# USB.net
KiCad netlist of a schematic drawn in Altium Designer
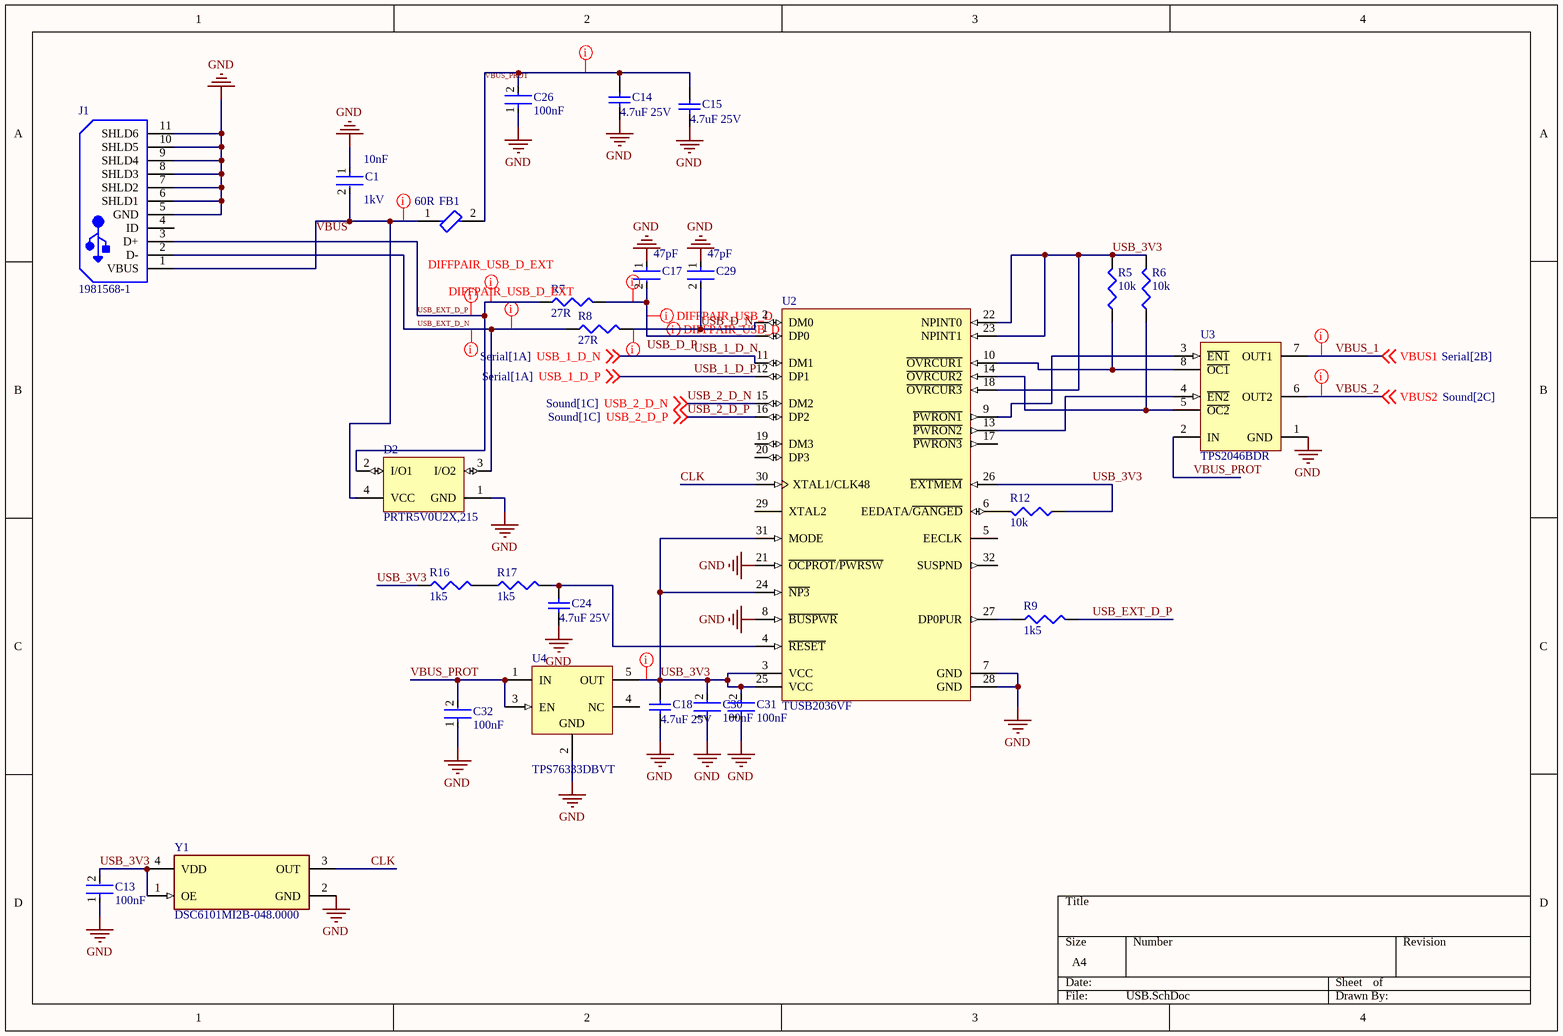
[diagram p0: USB.SchDoc]

(export (version "E")
  (design (tool "Eeschema 10.0.6"))
  (components
    (comp (ref "C1")
      (value "C4532X7R3A103K200KA")
      (footprint "FP-C4532-200-0_4-IPC_B")
      (description "Multilayer Ceramic Capacitors 10nF ±10% 1000V X7R SMD 1812")
      (fields
        (field (name "VOLTAGE RATING (DC)") "1kV")
        (field (name "TOLERANCE") "10%")
        (field (name "CAPACITANCE") "10nF")
        (field (name "JLCPCBPARTNUM") "C577346")
      )
      (libsource (lib "Altium Content Vault") (part "02cd4be3c70576c341d710602a673aa"))
    )
    (comp (ref "C13")
      (value "CL10B104KC8NNNC")
      (footprint "FP-CL10-IPC_B")
      (description "Cap Ceramic 100nF 100V X7R ±10% Pad SMD 0603 +125°C T/R")
      (fields
        (field (name "TOLERANCE") "10%")
        (field (name "CAPACITANCE") "100nF")
        (field (name "JLCPCBPARTNUM") "C15725")
      )
      (libsource (lib "Altium Content Vault") (part "b4654b650e69147ec39a6b967a45e02"))
    )
    (comp (ref "C14")
      (value "4.7uF 25V")
      (footprint "CAPC1210(3225)220_M")
      (description "CAP 4.7uF 25V ±10% 1210 (3225 Metric) Thickness 2.2mm SMD")
      (fields (field (name "TOLERANCE") "Â±10%") (field (name "JLCPCBPARTNUM") "C86052"))
      (libsource (lib "Altium Content Vault") (part "CAP"))
    )
    (comp (ref "C15")
      (value "4.7uF 25V")
      (footprint "CAPC1210(3225)220_M")
      (description "CAP 4.7uF 25V ±10% 1210 (3225 Metric) Thickness 2.2mm SMD")
      (fields (field (name "TOLERANCE") "Â±10%") (field (name "JLCPCBPARTNUM") "C86052"))
      (libsource (lib "Altium Content Vault") (part "CAP"))
    )
    (comp (ref "C17")
      (value "CL10C470JC8NNNC")
      (footprint "FP-CL10-IPC_C")
      (description "Cap Ceramic 47pF 100V C0G ±5% Pad SMD 0603 +125°C T/R")
      (fields
        (field (name "TOLERANCE") "5%")
        (field (name "CAPACITANCE") "47pF")
        (field (name "JLCPCBPARTNUM") "C1671")
      )
      (libsource (lib "Altium Content Vault") (part "b4654b650e69147ec39a6b967a45e02"))
    )
    (comp (ref "C18")
      (value "4.7uF 25V")
      (footprint "CAPC1210(3225)220_M")
      (description "CAP 4.7uF 25V ±10% 1210 (3225 Metric) Thickness 2.2mm SMD")
      (fields (field (name "TOLERANCE") "Â±10%") (field (name "JLCPCBPARTNUM") "C86052"))
      (libsource (lib "Altium Content Vault") (part "CAP"))
    )
    (comp (ref "C24")
      (value "4.7uF 25V")
      (footprint "CAPC1210(3225)220_M")
      (description "CAP 4.7uF 25V ±10% 1210 (3225 Metric) Thickness 2.2mm SMD")
      (fields (field (name "TOLERANCE") "Â±10%") (field (name "JLCPCBPARTNUM") "C86052"))
      (libsource (lib "Altium Content Vault") (part "CAP"))
    )
    (comp (ref "C26")
      (value "CL10B104KC8NNNC")
      (footprint "FP-CL10-IPC_B")
      (description "Cap Ceramic 100nF 100V X7R ±10% Pad SMD 0603 +125°C T/R")
      (fields
        (field (name "TOLERANCE") "10%")
        (field (name "CAPACITANCE") "100nF")
        (field (name "JLCPCBPARTNUM") "C15725")
      )
      (libsource (lib "Altium Content Vault") (part "b4654b650e69147ec39a6b967a45e02"))
    )
    (comp (ref "C29")
      (value "CL10C470JC8NNNC")
      (footprint "FP-CL10-IPC_C")
      (description "Cap Ceramic 47pF 100V C0G ±5% Pad SMD 0603 +125°C T/R")
      (fields
        (field (name "TOLERANCE") "5%")
        (field (name "CAPACITANCE") "47pF")
        (field (name "JLCPCBPARTNUM") "C1671")
      )
      (libsource (lib "Altium Content Vault") (part "b4654b650e69147ec39a6b967a45e02"))
    )
    (comp (ref "C30")
      (value "CL10B104KC8NNNC")
      (footprint "FP-CL10-IPC_B")
      (description "Cap Ceramic 100nF 100V X7R ±10% Pad SMD 0603 +125°C T/R")
      (fields
        (field (name "TOLERANCE") "10%")
        (field (name "CAPACITANCE") "100nF")
        (field (name "JLCPCBPARTNUM") "C15725")
      )
      (libsource (lib "Altium Content Vault") (part "b4654b650e69147ec39a6b967a45e02"))
    )
    (comp (ref "C31")
      (value "CL10B104KC8NNNC")
      (footprint "FP-CL10-IPC_B")
      (description "Cap Ceramic 100nF 100V X7R ±10% Pad SMD 0603 +125°C T/R")
      (fields
        (field (name "TOLERANCE") "10%")
        (field (name "CAPACITANCE") "100nF")
        (field (name "JLCPCBPARTNUM") "C15725")
      )
      (libsource (lib "Altium Content Vault") (part "b4654b650e69147ec39a6b967a45e02"))
    )
    (comp (ref "C32")
      (value "CL10B104KC8NNNC")
      (footprint "FP-CL10-IPC_B")
      (description "Cap Ceramic 100nF 100V X7R ±10% Pad SMD 0603 +125°C T/R")
      (fields
        (field (name "TOLERANCE") "10%")
        (field (name "CAPACITANCE") "100nF")
        (field (name "JLCPCBPARTNUM") "C15725")
      )
      (libsource (lib "Altium Content Vault") (part "b4654b650e69147ec39a6b967a45e02"))
    )
    (comp (ref "D2")
      (value "PRTR5V0U2X,215")
      (footprint "NXP-SOT143B-4_V")
      (fields (field (name "MANUFACTURER") "NXP Semiconductors") (field (name "JLCPCBPARTNUM") "C12333"))
      (libsource (lib "Altium Content Vault") (part "NXP-PRTR5V0U2X,215-4"))
    )
    (comp (ref "FB1")
      (value "BLM41PG600SN1L")
      (footprint "FP-BLM41-0_2-IPC_B")
      (description "Ferrite Bead, 1806, 60Ω @ 100MHz, 0.009Ω, 6A")
      (fields
        (field (name "TOLERANCE") "25%")
        (field (name "IMPEDANCE") "60R")
        (field (name "JLCPCBPARTNUM") "C85844")
      )
      (libsource (lib "Altium Content Vault") (part "5f30dd21d616792df468990f7003faa"))
    )
    (comp (ref "J1")
      (value "1981568-1")
      (footprint "TECO-1981568-5_V")
      (description "Micro USB Receptacle Standard Type B Assy, 5-Pin SMD, RoHS, Tape and Reel")
      (fields (field (name "MANUFACTURER") "TE Connectivity") (field (name "JLCPCBPARTNUM") "C428487"))
      (libsource (lib "Altium Content Vault") (part "USB-5-6SHLD"))
    )
    (comp (ref "R5")
      (value "10k")
      (footprint "J1-0603")
      (description "Resistor")
      (fields (field (name "JLCPCBPARTNUM") "C25804") (field (name "PUBLISHER") "Altium Limited"))
      (libsource (lib "Miscellaneous Devices") (part "Res3"))
    )
    (comp (ref "R6")
      (value "10k")
      (footprint "J1-0603")
      (description "Resistor")
      (fields (field (name "JLCPCBPARTNUM") "C25804") (field (name "PUBLISHER") "Altium Limited"))
      (libsource (lib "Miscellaneous Devices") (part "Res3"))
    )
    (comp (ref "R7")
      (value "27R")
      (footprint "J1-0603")
      (description "Resistor")
      (fields (field (name "JLCPCBPARTNUM") "C192531") (field (name "PUBLISHER") "Altium Limited"))
      (libsource (lib "Miscellaneous Devices") (part "Res3"))
    )
    (comp (ref "R8")
      (value "27R")
      (footprint "J1-0603")
      (description "Resistor")
      (fields (field (name "JLCPCBPARTNUM") "C192531") (field (name "PUBLISHER") "Altium Limited"))
      (libsource (lib "Miscellaneous Devices") (part "Res3"))
    )
    (comp (ref "R9")
      (value "1k5")
      (footprint "J1-0603")
      (description "Resistor")
      (fields (field (name "JLCPCBPARTNUM") "C192164") (field (name "PUBLISHER") "Altium Limited"))
      (libsource (lib "Miscellaneous Devices") (part "Res3"))
    )
    (comp (ref "R12")
      (value "10k")
      (footprint "J1-0603")
      (description "Resistor")
      (fields (field (name "JLCPCBPARTNUM") "C25804") (field (name "PUBLISHER") "Altium Limited"))
      (libsource (lib "Miscellaneous Devices") (part "Res3"))
    )
    (comp (ref "R16")
      (value "1k5")
      (footprint "J1-0603")
      (description "Resistor")
      (fields (field (name "JLCPCBPARTNUM") "C192164") (field (name "PUBLISHER") "Altium Limited"))
      (libsource (lib "Miscellaneous Devices") (part "Res3"))
    )
    (comp (ref "R17")
      (value "1k5")
      (footprint "J1-0603")
      (description "Resistor")
      (fields (field (name "JLCPCBPARTNUM") "C192164") (field (name "PUBLISHER") "Altium Limited"))
      (libsource (lib "Miscellaneous Devices") (part "Res3"))
    )
    (comp (ref "U2")
      (value "TUSB2036VF")
      (footprint "VF0032A_N")
      (fields (field (name "MANUFACTURER") "Texas Instruments") (field (name "JLCPCBPARTNUM") "C43665"))
      (libsource (lib "Altium Content Vault") (part "TI-TUSB2036-LQFP_VF-32"))
    )
    (comp (ref "U3")
      (value "TPS2046BDR")
      (footprint "D0008A_L")
      (fields (field (name "MANUFACTURER") "Texas Instruments"))
      (libsource (lib "Altium Content Vault") (part "TI-TPS2046BD8"))
    )
    (comp (ref "U4")
      (value "TPS76333DBVT")
      (footprint "DBV0005A_N")
      (fields (field (name "MANUFACTURER") "Texas Instruments") (field (name "JLCPCBPARTNUM") "C7100"))
      (libsource (lib "Altium Content Vault") (part "TI-TXX7XXXX-5"))
    )
    (comp (ref "Y1")
      (value "DSC6101MI2B-048.0000")
      (footprint "FP-C04-C04-1200-0")
      (description "MEMS OSC XO 48.0000MHZ CMOS SMD")
      (fields
        (field (name "MANUFACTURER PART NUMBER") "DSC6101MI2A-024.0000T")
        (field (name "MANUFACTURER") "Microchip")
      )
      (libsource (lib "Altium Content Vault") (part "8e0094c34f88b5d5b38204ecca5ea85"))
    )
  )
  (nets
    (net (code "1") (name "/CLK") (class "Default")
      (node (ref "U2") (pin "30") (pinfunction "XTAL1/CLK48_30") (pintype "input"))
      (node (ref "Y1") (pin "3") (pinfunction "OUT_3") (pintype "passive"))
    )
    (net (code "2") (name "/USB_3V3") (class "Default")
      (node (ref "C13") (pin "2") (pinfunction "2_2") (pintype "passive"))
      (node (ref "C18") (pin "2") (pinfunction "2_2") (pintype "passive"))
      (node (ref "C30") (pin "2") (pinfunction "2_2") (pintype "passive"))
      (node (ref "C31") (pin "2") (pinfunction "2_2") (pintype "passive"))
      (node (ref "R12") (pin "1") (pinfunction "1_1") (pintype "passive"))
      (node (ref "R16") (pin "1") (pinfunction "1_1") (pintype "passive"))
      (node (ref "R5") (pin "2") (pinfunction "2_2") (pintype "passive"))
      (node (ref "R6") (pin "2") (pinfunction "2_2") (pintype "passive"))
      (node (ref "U2") (pin "18") (pinfunction "~{OVRCUR3}_18") (pintype "input"))
      (node (ref "U2") (pin "22") (pinfunction "NPINT0_22") (pintype "input"))
      (node (ref "U2") (pin "23") (pinfunction "NPINT1_23") (pintype "input"))
      (node (ref "U2") (pin "24") (pinfunction "~{NP3}_24") (pintype "input"))
      (node (ref "U2") (pin "25") (pinfunction "VCC_25") (pintype "power_in"))
      (node (ref "U2") (pin "26") (pinfunction "~{EXTMEM}_26") (pintype "input"))
      (node (ref "U2") (pin "3") (pinfunction "VCC_3") (pintype "power_in"))
      (node (ref "U2") (pin "31") (pinfunction "MODE_31") (pintype "input"))
      (node (ref "U4") (pin "5") (pinfunction "OUT_5") (pintype "power_in"))
      (node (ref "Y1") (pin "1") (pinfunction "OE_1") (pintype "input"))
      (node (ref "Y1") (pin "4") (pinfunction "VDD_4") (pintype "power_in"))
    )
    (net (code "3") (name "/USB_D_N") (class "Default")
      (node (ref "C29") (pin "2") (pinfunction "2_2") (pintype "passive"))
      (node (ref "R8") (pin "2") (pinfunction "2_2") (pintype "passive"))
      (node (ref "U2") (pin "2") (pinfunction "DM0_2") (pintype "bidirectional"))
    )
    (net (code "4") (name "/USB_D_P") (class "Default")
      (node (ref "C17") (pin "2") (pinfunction "2_2") (pintype "passive"))
      (node (ref "R7") (pin "2") (pinfunction "2_2") (pintype "passive"))
      (node (ref "U2") (pin "1") (pinfunction "DP0_1") (pintype "bidirectional"))
    )
    (net (code "5") (name "/USB_EXT_D_N") (class "Default")
      (node (ref "D2") (pin "3") (pinfunction "I/O2_3") (pintype "bidirectional"))
      (node (ref "J1") (pin "2") (pinfunction "D-_2") (pintype "passive"))
      (node (ref "R8") (pin "1") (pinfunction "1_1") (pintype "passive"))
    )
    (net (code "6") (name "/USB_EXT_D_P") (class "Default")
      (node (ref "D2") (pin "2") (pinfunction "I/O1_2") (pintype "bidirectional"))
      (node (ref "J1") (pin "3") (pinfunction "D+_3") (pintype "passive"))
      (node (ref "R7") (pin "1") (pinfunction "1_1") (pintype "passive"))
      (node (ref "R9") (pin "2") (pinfunction "2_2") (pintype "passive"))
    )
    (net (code "7") (name "/VBUS") (class "Default")
      (node (ref "C1") (pin "2") (pinfunction "2_2") (pintype "passive"))
      (node (ref "D2") (pin "4") (pinfunction "VCC_4") (pintype "power_in"))
      (node (ref "FB1") (pin "1") (pinfunction "1_1") (pintype "passive"))
      (node (ref "J1") (pin "1") (pinfunction "VBUS_1") (pintype "passive"))
    )
    (net (code "8") (name "/VBUS_PROT") (class "Default")
      (node (ref "C14") (pin "2") (pinfunction "2_2") (pintype "passive"))
      (node (ref "C15") (pin "2") (pinfunction "2_2") (pintype "passive"))
      (node (ref "C26") (pin "2") (pinfunction "2_2") (pintype "passive"))
      (node (ref "C32") (pin "2") (pinfunction "2_2") (pintype "passive"))
      (node (ref "FB1") (pin "2") (pinfunction "2_2") (pintype "passive"))
      (node (ref "U3") (pin "2") (pinfunction "IN_2") (pintype "power_in"))
      (node (ref "U4") (pin "1") (pinfunction "IN_1") (pintype "power_in"))
      (node (ref "U4") (pin "3") (pinfunction "EN_3") (pintype "input"))
    )
    (net (code "9") (name "GND") (class "Default")
      (node (ref "C1") (pin "1") (pinfunction "1_1") (pintype "passive"))
      (node (ref "C13") (pin "1") (pinfunction "1_1") (pintype "passive"))
      (node (ref "C14") (pin "1") (pinfunction "1_1") (pintype "passive"))
      (node (ref "C15") (pin "1") (pinfunction "1_1") (pintype "passive"))
      (node (ref "C17") (pin "1") (pinfunction "1_1") (pintype "passive"))
      (node (ref "C18") (pin "1") (pinfunction "1_1") (pintype "passive"))
      (node (ref "C24") (pin "1") (pinfunction "1_1") (pintype "passive"))
      (node (ref "C26") (pin "1") (pinfunction "1_1") (pintype "passive"))
      (node (ref "C29") (pin "1") (pinfunction "1_1") (pintype "passive"))
      (node (ref "C30") (pin "1") (pinfunction "1_1") (pintype "passive"))
      (node (ref "C31") (pin "1") (pinfunction "1_1") (pintype "passive"))
      (node (ref "C32") (pin "1") (pinfunction "1_1") (pintype "passive"))
      (node (ref "D2") (pin "1") (pinfunction "GND_1") (pintype "power_in"))
      (node (ref "J1") (pin "10") (pinfunction "SHLD5_10") (pintype "passive"))
      (node (ref "J1") (pin "11") (pinfunction "SHLD6_11") (pintype "passive"))
      (node (ref "J1") (pin "5") (pinfunction "GND_5") (pintype "passive"))
      (node (ref "J1") (pin "6") (pinfunction "SHLD1_6") (pintype "passive"))
      (node (ref "J1") (pin "7") (pinfunction "SHLD2_7") (pintype "passive"))
      (node (ref "J1") (pin "8") (pinfunction "SHLD3_8") (pintype "passive"))
      (node (ref "J1") (pin "9") (pinfunction "SHLD4_9") (pintype "passive"))
      (node (ref "U2") (pin "21") (pinfunction "~{OCPROT}/~{PWRSW}_21") (pintype "input"))
      (node (ref "U2") (pin "28") (pinfunction "GND_28") (pintype "power_in"))
      (node (ref "U2") (pin "7") (pinfunction "GND_7") (pintype "power_in"))
      (node (ref "U2") (pin "8") (pinfunction "~{BUSPWR}_8") (pintype "input"))
      (node (ref "U3") (pin "1") (pinfunction "GND_1") (pintype "power_in"))
      (node (ref "U4") (pin "2") (pinfunction "GND_2") (pintype "power_in"))
      (node (ref "Y1") (pin "2") (pinfunction "GND_2") (pintype "power_in"))
    )
    (net (code "10") (name "Net-(R16-Pad2)") (class "Default")
      (node (ref "R16") (pin "2") (pinfunction "2_2") (pintype "passive"))
      (node (ref "R17") (pin "1") (pinfunction "1_1") (pintype "passive"))
    )
    (net (code "11") (name "Net-(U2-DP0PUR)") (class "Default")
      (node (ref "R9") (pin "1") (pinfunction "1_1") (pintype "passive"))
      (node (ref "U2") (pin "27") (pinfunction "DP0PUR_27") (pintype "output"))
    )
    (net (code "12") (name "Net-(U2-EEDATA{slash}~{GANGED})") (class "Default")
      (node (ref "R12") (pin "2") (pinfunction "2_2") (pintype "passive"))
      (node (ref "U2") (pin "6") (pinfunction "EEDATA/~{GANGED}_6") (pintype "bidirectional"))
    )
    (net (code "13") (name "Net-(U2-~{OVRCUR1})") (class "Default")
      (node (ref "R5") (pin "1") (pinfunction "1_1") (pintype "passive"))
      (node (ref "U2") (pin "10") (pinfunction "~{OVRCUR1}_10") (pintype "input"))
      (node (ref "U3") (pin "8") (pinfunction "~{OC1}_8") (pintype "open_collector"))
    )
    (net (code "14") (name "Net-(U2-~{OVRCUR2})") (class "Default")
      (node (ref "R6") (pin "1") (pinfunction "1_1") (pintype "passive"))
      (node (ref "U2") (pin "14") (pinfunction "~{OVRCUR2}_14") (pintype "input"))
      (node (ref "U3") (pin "5") (pinfunction "~{OC2}_5") (pintype "open_collector"))
    )
    (net (code "15") (name "Net-(U2-~{PWRON1})") (class "Default")
      (node (ref "U2") (pin "9") (pinfunction "~{PWRON1}_9") (pintype "output"))
      (node (ref "U3") (pin "3") (pinfunction "~{EN1}_3") (pintype "input"))
    )
    (net (code "16") (name "Net-(U2-~{PWRON2})") (class "Default")
      (node (ref "U2") (pin "13") (pinfunction "~{PWRON2}_13") (pintype "output"))
      (node (ref "U3") (pin "4") (pinfunction "~{EN2}_4") (pintype "input"))
    )
    (net (code "17") (name "Net-(U2-~{RESET})") (class "Default")
      (node (ref "C24") (pin "2") (pinfunction "2_2") (pintype "passive"))
      (node (ref "R17") (pin "2") (pinfunction "2_2") (pintype "passive"))
      (node (ref "U2") (pin "4") (pinfunction "~{RESET}_4") (pintype "input"))
    )
    (net (code "18") (name "USB_1_D_N") (class "Default")
      (node (ref "U2") (pin "11") (pinfunction "DM1_11") (pintype "bidirectional"))
    )
    (net (code "19") (name "USB_1_D_P") (class "Default")
      (node (ref "U2") (pin "12") (pinfunction "DP1_12") (pintype "bidirectional"))
    )
    (net (code "20") (name "USB_2_D_N") (class "Default")
      (node (ref "U2") (pin "15") (pinfunction "DM2_15") (pintype "bidirectional"))
    )
    (net (code "21") (name "USB_2_D_P") (class "Default")
      (node (ref "U2") (pin "16") (pinfunction "DP2_16") (pintype "bidirectional"))
    )
    (net (code "22") (name "VBUS1") (class "Default")
      (node (ref "U3") (pin "7") (pinfunction "OUT1_7") (pintype "power_in"))
    )
    (net (code "23") (name "VBUS2") (class "Default")
      (node (ref "U3") (pin "6") (pinfunction "OUT2_6") (pintype "power_in"))
    )
    (net (code "24") (name "unconnected-(J1-ID-Pad4)") (class "Default")
      (node (ref "J1") (pin "4") (pinfunction "ID_4") (pintype "passive"))
    )
    (net (code "25") (name "unconnected-(U2-DM3-Pad19)") (class "Default")
      (node (ref "U2") (pin "19") (pinfunction "DM3_19") (pintype "bidirectional"))
    )
    (net (code "26") (name "unconnected-(U2-DP3-Pad20)") (class "Default")
      (node (ref "U2") (pin "20") (pinfunction "DP3_20") (pintype "bidirectional"))
    )
    (net (code "27") (name "unconnected-(U2-EECLK-Pad5)") (class "Default")
      (node (ref "U2") (pin "5") (pinfunction "EECLK_5") (pintype "tri_state"))
    )
    (net (code "28") (name "unconnected-(U2-SUSPND-Pad32)") (class "Default")
      (node (ref "U2") (pin "32") (pinfunction "SUSPND_32") (pintype "output"))
    )
    (net (code "29") (name "unconnected-(U2-XTAL2-Pad29)") (class "Default")
      (node (ref "U2") (pin "29") (pinfunction "XTAL2_29") (pintype "passive"))
    )
    (net (code "30") (name "unconnected-(U2-~{PWRON3}-Pad17)") (class "Default")
      (node (ref "U2") (pin "17") (pinfunction "~{PWRON3}_17") (pintype "output"))
    )
    (net (code "31") (name "unconnected-(U4-NC-Pad4)") (class "Default")
      (node (ref "U4") (pin "4") (pinfunction "NC_4") (pintype "passive"))
    )
  )
)
